# blink1-ws2812-adapter2f.net
KiCad netlist of a schematic drawn in EAGLE
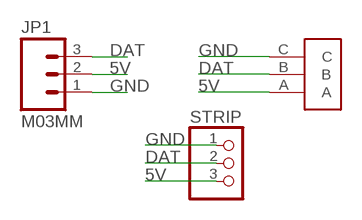
[diagram p0: schematic, sheet 1]

(export (version "E")
  (design (tool "Eeschema 10.0.6"))
  (components
    (comp (ref "JP1")
      (value "M03MM")
      (footprint "eagle-import:1X03-1.5MM")
      (libsource (lib "eagle-import") (part "M03MM"))
    )
    (comp (ref "STRIP")
      (value "PINHD-1X3")
      (footprint "eagle-import:1X03")
      (libsource (lib "eagle-import") (part "PINHD-1X3"))
    )
    (comp (ref "U$1")
      (value "LED_STRIP_3P")
      (footprint "eagle-import:LEDSTRIP-3P")
      (libsource (lib "eagle-import") (part "LED_STRIP_3P"))
    )
  )
  (nets
    (net (code "1") (name "/5V") (class "Default")
      (node (ref "JP1") (pin "2") (pinfunction "2_2") (pintype "passive"))
      (node (ref "STRIP") (pin "3") (pinfunction "3_3") (pintype "passive"))
      (node (ref "U$1") (pin "A") (pinfunction "A_A") (pintype "bidirectional"))
    )
    (net (code "2") (name "/DAT") (class "Default")
      (node (ref "JP1") (pin "3") (pinfunction "3_3") (pintype "passive"))
      (node (ref "STRIP") (pin "2") (pinfunction "2_2") (pintype "passive"))
      (node (ref "U$1") (pin "B") (pinfunction "B_B") (pintype "bidirectional"))
    )
    (net (code "3") (name "/GND") (class "Default")
      (node (ref "JP1") (pin "1") (pinfunction "1_1") (pintype "passive"))
      (node (ref "STRIP") (pin "1") (pinfunction "1_1") (pintype "passive"))
      (node (ref "U$1") (pin "C") (pinfunction "C_C") (pintype "bidirectional"))
    )
  )
)
